# v2.net
KiCad netlist of a schematic drawn in Altium Designer
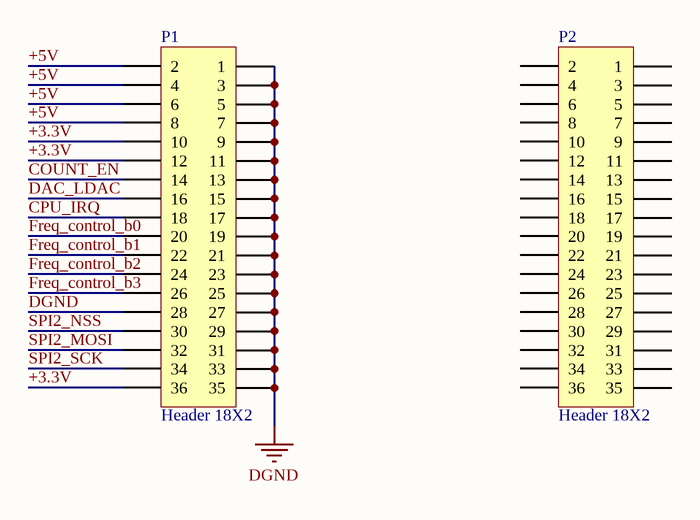
[diagram p0: v2.SchDoc]

(export (version "E")
  (design (tool "Eeschema 10.0.6"))
  (components
    (comp (ref "P1")
      (value "Header 18X2")
      (footprint "HDR2X18")
      (description "Header, 18-Pin, Dual row")
      (fields (field (name "PUBLISHER") "Altium Limited"))
      (libsource (lib "Miscellaneous Connectors") (part "Header 18X2"))
    )
    (comp (ref "P2")
      (value "Header 18X2")
      (footprint "HDR2X18")
      (description "Header, 18-Pin, Dual row")
      (fields (field (name "PUBLISHER") "Altium Limited"))
      (libsource (lib "Miscellaneous Connectors") (part "Header 18X2"))
    )
  )
  (nets
    (net (code "1") (name "/+3.3V") (class "Default")
      (node (ref "P1") (pin "10") (pinfunction "10_10") (pintype "passive"))
      (node (ref "P1") (pin "12") (pinfunction "12_12") (pintype "passive"))
      (node (ref "P1") (pin "36") (pinfunction "36_36") (pintype "passive"))
    )
    (net (code "2") (name "/+5V") (class "Default")
      (node (ref "P1") (pin "2") (pinfunction "2_2") (pintype "passive"))
      (node (ref "P1") (pin "4") (pinfunction "4_4") (pintype "passive"))
      (node (ref "P1") (pin "6") (pinfunction "6_6") (pintype "passive"))
      (node (ref "P1") (pin "8") (pinfunction "8_8") (pintype "passive"))
    )
    (net (code "3") (name "/COUNT_EN") (class "Default")
      (node (ref "P1") (pin "14") (pinfunction "14_14") (pintype "passive"))
    )
    (net (code "4") (name "/CPU_IRQ") (class "Default")
      (node (ref "P1") (pin "18") (pinfunction "18_18") (pintype "passive"))
    )
    (net (code "5") (name "/DAC_LDAC") (class "Default")
      (node (ref "P1") (pin "16") (pinfunction "16_16") (pintype "passive"))
    )
    (net (code "6") (name "/Freq_control_b0") (class "Default")
      (node (ref "P1") (pin "20") (pinfunction "20_20") (pintype "passive"))
    )
    (net (code "7") (name "/Freq_control_b1") (class "Default")
      (node (ref "P1") (pin "22") (pinfunction "22_22") (pintype "passive"))
    )
    (net (code "8") (name "/Freq_control_b2") (class "Default")
      (node (ref "P1") (pin "24") (pinfunction "24_24") (pintype "passive"))
    )
    (net (code "9") (name "/Freq_control_b3") (class "Default")
      (node (ref "P1") (pin "26") (pinfunction "26_26") (pintype "passive"))
    )
    (net (code "10") (name "/SPI2_MOSI") (class "Default")
      (node (ref "P1") (pin "32") (pinfunction "32_32") (pintype "passive"))
    )
    (net (code "11") (name "/SPI2_NSS") (class "Default")
      (node (ref "P1") (pin "30") (pinfunction "30_30") (pintype "passive"))
    )
    (net (code "12") (name "/SPI2_SCK") (class "Default")
      (node (ref "P1") (pin "34") (pinfunction "34_34") (pintype "passive"))
    )
    (net (code "13") (name "DGND") (class "Default")
      (node (ref "P1") (pin "1") (pinfunction "1_1") (pintype "passive"))
      (node (ref "P1") (pin "11") (pinfunction "11_11") (pintype "passive"))
      (node (ref "P1") (pin "13") (pinfunction "13_13") (pintype "passive"))
      (node (ref "P1") (pin "15") (pinfunction "15_15") (pintype "passive"))
      (node (ref "P1") (pin "17") (pinfunction "17_17") (pintype "passive"))
      (node (ref "P1") (pin "19") (pinfunction "19_19") (pintype "passive"))
      (node (ref "P1") (pin "21") (pinfunction "21_21") (pintype "passive"))
      (node (ref "P1") (pin "23") (pinfunction "23_23") (pintype "passive"))
      (node (ref "P1") (pin "25") (pinfunction "25_25") (pintype "passive"))
      (node (ref "P1") (pin "27") (pinfunction "27_27") (pintype "passive"))
      (node (ref "P1") (pin "28") (pinfunction "28_28") (pintype "passive"))
      (node (ref "P1") (pin "29") (pinfunction "29_29") (pintype "passive"))
      (node (ref "P1") (pin "3") (pinfunction "3_3") (pintype "passive"))
      (node (ref "P1") (pin "31") (pinfunction "31_31") (pintype "passive"))
      (node (ref "P1") (pin "33") (pinfunction "33_33") (pintype "passive"))
      (node (ref "P1") (pin "35") (pinfunction "35_35") (pintype "passive"))
      (node (ref "P1") (pin "5") (pinfunction "5_5") (pintype "passive"))
      (node (ref "P1") (pin "7") (pinfunction "7_7") (pintype "passive"))
      (node (ref "P1") (pin "9") (pinfunction "9_9") (pintype "passive"))
    )
    (net (code "14") (name "unconnected-(P2-Pad1)") (class "Default")
      (node (ref "P2") (pin "1") (pinfunction "1_1") (pintype "passive"))
    )
    (net (code "15") (name "unconnected-(P2-Pad2)") (class "Default")
      (node (ref "P2") (pin "2") (pinfunction "2_2") (pintype "passive"))
    )
    (net (code "16") (name "unconnected-(P2-Pad3)") (class "Default")
      (node (ref "P2") (pin "3") (pinfunction "3_3") (pintype "passive"))
    )
    (net (code "17") (name "unconnected-(P2-Pad4)") (class "Default")
      (node (ref "P2") (pin "4") (pinfunction "4_4") (pintype "passive"))
    )
    (net (code "18") (name "unconnected-(P2-Pad5)") (class "Default")
      (node (ref "P2") (pin "5") (pinfunction "5_5") (pintype "passive"))
    )
    (net (code "19") (name "unconnected-(P2-Pad6)") (class "Default")
      (node (ref "P2") (pin "6") (pinfunction "6_6") (pintype "passive"))
    )
    (net (code "20") (name "unconnected-(P2-Pad7)") (class "Default")
      (node (ref "P2") (pin "7") (pinfunction "7_7") (pintype "passive"))
    )
    (net (code "21") (name "unconnected-(P2-Pad8)") (class "Default")
      (node (ref "P2") (pin "8") (pinfunction "8_8") (pintype "passive"))
    )
    (net (code "22") (name "unconnected-(P2-Pad9)") (class "Default")
      (node (ref "P2") (pin "9") (pinfunction "9_9") (pintype "passive"))
    )
    (net (code "23") (name "unconnected-(P2-Pad10)") (class "Default")
      (node (ref "P2") (pin "10") (pinfunction "10_10") (pintype "passive"))
    )
    (net (code "24") (name "unconnected-(P2-Pad11)") (class "Default")
      (node (ref "P2") (pin "11") (pinfunction "11_11") (pintype "passive"))
    )
    (net (code "25") (name "unconnected-(P2-Pad12)") (class "Default")
      (node (ref "P2") (pin "12") (pinfunction "12_12") (pintype "passive"))
    )
    (net (code "26") (name "unconnected-(P2-Pad13)") (class "Default")
      (node (ref "P2") (pin "13") (pinfunction "13_13") (pintype "passive"))
    )
    (net (code "27") (name "unconnected-(P2-Pad14)") (class "Default")
      (node (ref "P2") (pin "14") (pinfunction "14_14") (pintype "passive"))
    )
    (net (code "28") (name "unconnected-(P2-Pad15)") (class "Default")
      (node (ref "P2") (pin "15") (pinfunction "15_15") (pintype "passive"))
    )
    (net (code "29") (name "unconnected-(P2-Pad16)") (class "Default")
      (node (ref "P2") (pin "16") (pinfunction "16_16") (pintype "passive"))
    )
    (net (code "30") (name "unconnected-(P2-Pad17)") (class "Default")
      (node (ref "P2") (pin "17") (pinfunction "17_17") (pintype "passive"))
    )
    (net (code "31") (name "unconnected-(P2-Pad18)") (class "Default")
      (node (ref "P2") (pin "18") (pinfunction "18_18") (pintype "passive"))
    )
    (net (code "32") (name "unconnected-(P2-Pad19)") (class "Default")
      (node (ref "P2") (pin "19") (pinfunction "19_19") (pintype "passive"))
    )
    (net (code "33") (name "unconnected-(P2-Pad20)") (class "Default")
      (node (ref "P2") (pin "20") (pinfunction "20_20") (pintype "passive"))
    )
    (net (code "34") (name "unconnected-(P2-Pad21)") (class "Default")
      (node (ref "P2") (pin "21") (pinfunction "21_21") (pintype "passive"))
    )
    (net (code "35") (name "unconnected-(P2-Pad22)") (class "Default")
      (node (ref "P2") (pin "22") (pinfunction "22_22") (pintype "passive"))
    )
    (net (code "36") (name "unconnected-(P2-Pad23)") (class "Default")
      (node (ref "P2") (pin "23") (pinfunction "23_23") (pintype "passive"))
    )
    (net (code "37") (name "unconnected-(P2-Pad24)") (class "Default")
      (node (ref "P2") (pin "24") (pinfunction "24_24") (pintype "passive"))
    )
    (net (code "38") (name "unconnected-(P2-Pad25)") (class "Default")
      (node (ref "P2") (pin "25") (pinfunction "25_25") (pintype "passive"))
    )
    (net (code "39") (name "unconnected-(P2-Pad26)") (class "Default")
      (node (ref "P2") (pin "26") (pinfunction "26_26") (pintype "passive"))
    )
    (net (code "40") (name "unconnected-(P2-Pad27)") (class "Default")
      (node (ref "P2") (pin "27") (pinfunction "27_27") (pintype "passive"))
    )
    (net (code "41") (name "unconnected-(P2-Pad28)") (class "Default")
      (node (ref "P2") (pin "28") (pinfunction "28_28") (pintype "passive"))
    )
    (net (code "42") (name "unconnected-(P2-Pad29)") (class "Default")
      (node (ref "P2") (pin "29") (pinfunction "29_29") (pintype "passive"))
    )
    (net (code "43") (name "unconnected-(P2-Pad30)") (class "Default")
      (node (ref "P2") (pin "30") (pinfunction "30_30") (pintype "passive"))
    )
    (net (code "44") (name "unconnected-(P2-Pad31)") (class "Default")
      (node (ref "P2") (pin "31") (pinfunction "31_31") (pintype "passive"))
    )
    (net (code "45") (name "unconnected-(P2-Pad32)") (class "Default")
      (node (ref "P2") (pin "32") (pinfunction "32_32") (pintype "passive"))
    )
    (net (code "46") (name "unconnected-(P2-Pad33)") (class "Default")
      (node (ref "P2") (pin "33") (pinfunction "33_33") (pintype "passive"))
    )
    (net (code "47") (name "unconnected-(P2-Pad34)") (class "Default")
      (node (ref "P2") (pin "34") (pinfunction "34_34") (pintype "passive"))
    )
    (net (code "48") (name "unconnected-(P2-Pad35)") (class "Default")
      (node (ref "P2") (pin "35") (pinfunction "35_35") (pintype "passive"))
    )
    (net (code "49") (name "unconnected-(P2-Pad36)") (class "Default")
      (node (ref "P2") (pin "36") (pinfunction "36_36") (pintype "passive"))
    )
  )
)
